# 05_LEDs.net
KiCad netlist of a schematic drawn in Altium Designer
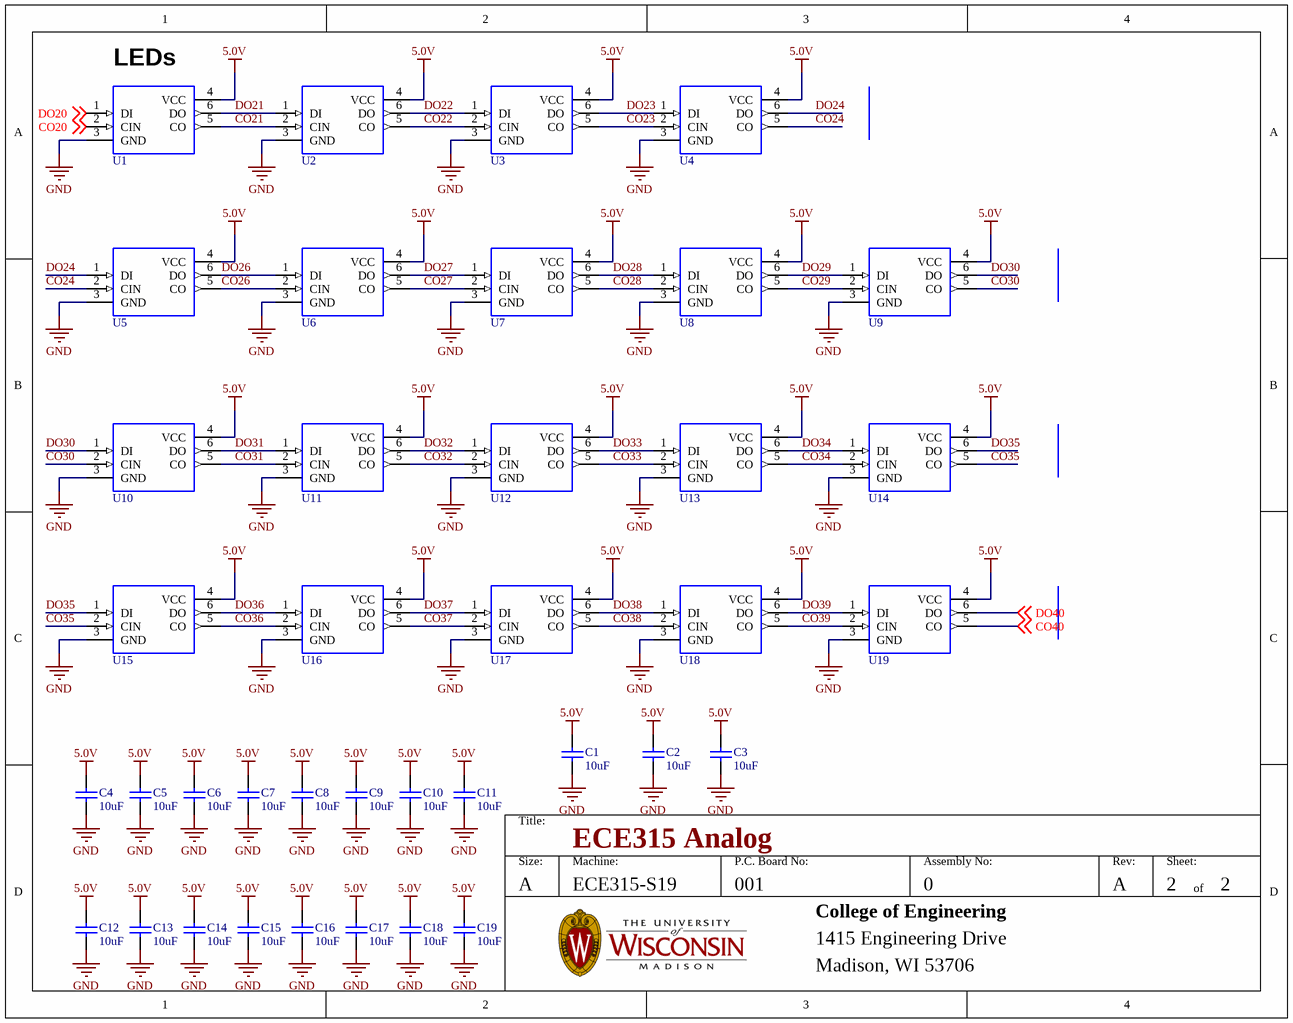
[diagram p0: 05_LEDs.SchDoc]

(export (version "E")
  (design (tool "Eeschema 10.0.6"))
  (components
    (comp (ref "C1")
      (value "10uF")
      (footprint "CAP_0805")
      (description "CAP CER 10UF 16V X7R 0805")
      (fields
        (field (name "MANUFACTURER") "Samsung")
        (field (name "MANUFACTURER PART NUMBER") "CL21A106KPCLQNC")
        (field (name "CAPACITANCE") "10uF")
      )
      (libsource (lib "ece315-2018-fall") (part "CAP_0805_U_010.00"))
    )
    (comp (ref "C2")
      (value "10uF")
      (footprint "CAP_0805")
      (description "CAP CER 10UF 16V X7R 0805")
      (fields
        (field (name "MANUFACTURER") "Samsung")
        (field (name "MANUFACTURER PART NUMBER") "CL21A106KPCLQNC")
        (field (name "CAPACITANCE") "10uF")
      )
      (libsource (lib "ece315-2018-fall") (part "CAP_0805_U_010.00"))
    )
    (comp (ref "C3")
      (value "10uF")
      (footprint "CAP_0805")
      (description "CAP CER 10UF 16V X7R 0805")
      (fields
        (field (name "MANUFACTURER") "Samsung")
        (field (name "MANUFACTURER PART NUMBER") "CL21A106KPCLQNC")
        (field (name "CAPACITANCE") "10uF")
      )
      (libsource (lib "ece315-2018-fall") (part "CAP_0805_U_010.00"))
    )
    (comp (ref "C4")
      (value "10uF")
      (footprint "CAP_0805")
      (description "CAP CER 10UF 16V X7R 0805")
      (fields
        (field (name "MANUFACTURER") "Samsung")
        (field (name "MANUFACTURER PART NUMBER") "CL21A106KPCLQNC")
        (field (name "CAPACITANCE") "10uF")
      )
      (libsource (lib "ece315-2018-fall") (part "CAP_0805_U_010.00"))
    )
    (comp (ref "C5")
      (value "10uF")
      (footprint "CAP_0805")
      (description "CAP CER 10UF 16V X7R 0805")
      (fields
        (field (name "MANUFACTURER") "Samsung")
        (field (name "MANUFACTURER PART NUMBER") "CL21A106KPCLQNC")
        (field (name "CAPACITANCE") "10uF")
      )
      (libsource (lib "ece315-2018-fall") (part "CAP_0805_U_010.00"))
    )
    (comp (ref "C6")
      (value "10uF")
      (footprint "CAP_0805")
      (description "CAP CER 10UF 16V X7R 0805")
      (fields
        (field (name "MANUFACTURER") "Samsung")
        (field (name "MANUFACTURER PART NUMBER") "CL21A106KPCLQNC")
        (field (name "CAPACITANCE") "10uF")
      )
      (libsource (lib "ece315-2018-fall") (part "CAP_0805_U_010.00"))
    )
    (comp (ref "C7")
      (value "10uF")
      (footprint "CAP_0805")
      (description "CAP CER 10UF 16V X7R 0805")
      (fields
        (field (name "MANUFACTURER") "Samsung")
        (field (name "MANUFACTURER PART NUMBER") "CL21A106KPCLQNC")
        (field (name "CAPACITANCE") "10uF")
      )
      (libsource (lib "ece315-2018-fall") (part "CAP_0805_U_010.00"))
    )
    (comp (ref "C8")
      (value "10uF")
      (footprint "CAP_0805")
      (description "CAP CER 10UF 16V X7R 0805")
      (fields
        (field (name "MANUFACTURER") "Samsung")
        (field (name "MANUFACTURER PART NUMBER") "CL21A106KPCLQNC")
        (field (name "CAPACITANCE") "10uF")
      )
      (libsource (lib "ece315-2018-fall") (part "CAP_0805_U_010.00"))
    )
    (comp (ref "C9")
      (value "10uF")
      (footprint "CAP_0805")
      (description "CAP CER 10UF 16V X7R 0805")
      (fields
        (field (name "MANUFACTURER") "Samsung")
        (field (name "MANUFACTURER PART NUMBER") "CL21A106KPCLQNC")
        (field (name "CAPACITANCE") "10uF")
      )
      (libsource (lib "ece315-2018-fall") (part "CAP_0805_U_010.00"))
    )
    (comp (ref "C10")
      (value "10uF")
      (footprint "CAP_0805")
      (description "CAP CER 10UF 16V X7R 0805")
      (fields
        (field (name "MANUFACTURER") "Samsung")
        (field (name "MANUFACTURER PART NUMBER") "CL21A106KPCLQNC")
        (field (name "CAPACITANCE") "10uF")
      )
      (libsource (lib "ece315-2018-fall") (part "CAP_0805_U_010.00"))
    )
    (comp (ref "C11")
      (value "10uF")
      (footprint "CAP_0805")
      (description "CAP CER 10UF 16V X7R 0805")
      (fields
        (field (name "MANUFACTURER") "Samsung")
        (field (name "MANUFACTURER PART NUMBER") "CL21A106KPCLQNC")
        (field (name "CAPACITANCE") "10uF")
      )
      (libsource (lib "ece315-2018-fall") (part "CAP_0805_U_010.00"))
    )
    (comp (ref "C12")
      (value "10uF")
      (footprint "CAP_0805")
      (description "CAP CER 10UF 16V X7R 0805")
      (fields
        (field (name "MANUFACTURER") "Samsung")
        (field (name "MANUFACTURER PART NUMBER") "CL21A106KPCLQNC")
        (field (name "CAPACITANCE") "10uF")
      )
      (libsource (lib "ece315-2018-fall") (part "CAP_0805_U_010.00"))
    )
    (comp (ref "C13")
      (value "10uF")
      (footprint "CAP_0805")
      (description "CAP CER 10UF 16V X7R 0805")
      (fields
        (field (name "MANUFACTURER") "Samsung")
        (field (name "MANUFACTURER PART NUMBER") "CL21A106KPCLQNC")
        (field (name "CAPACITANCE") "10uF")
      )
      (libsource (lib "ece315-2018-fall") (part "CAP_0805_U_010.00"))
    )
    (comp (ref "C14")
      (value "10uF")
      (footprint "CAP_0805")
      (description "CAP CER 10UF 16V X7R 0805")
      (fields
        (field (name "MANUFACTURER") "Samsung")
        (field (name "MANUFACTURER PART NUMBER") "CL21A106KPCLQNC")
        (field (name "CAPACITANCE") "10uF")
      )
      (libsource (lib "ece315-2018-fall") (part "CAP_0805_U_010.00"))
    )
    (comp (ref "C15")
      (value "10uF")
      (footprint "CAP_0805")
      (description "CAP CER 10UF 16V X7R 0805")
      (fields
        (field (name "MANUFACTURER") "Samsung")
        (field (name "MANUFACTURER PART NUMBER") "CL21A106KPCLQNC")
        (field (name "CAPACITANCE") "10uF")
      )
      (libsource (lib "ece315-2018-fall") (part "CAP_0805_U_010.00"))
    )
    (comp (ref "C16")
      (value "10uF")
      (footprint "CAP_0805")
      (description "CAP CER 10UF 16V X7R 0805")
      (fields
        (field (name "MANUFACTURER") "Samsung")
        (field (name "MANUFACTURER PART NUMBER") "CL21A106KPCLQNC")
        (field (name "CAPACITANCE") "10uF")
      )
      (libsource (lib "ece315-2018-fall") (part "CAP_0805_U_010.00"))
    )
    (comp (ref "C17")
      (value "10uF")
      (footprint "CAP_0805")
      (description "CAP CER 10UF 16V X7R 0805")
      (fields
        (field (name "MANUFACTURER") "Samsung")
        (field (name "MANUFACTURER PART NUMBER") "CL21A106KPCLQNC")
        (field (name "CAPACITANCE") "10uF")
      )
      (libsource (lib "ece315-2018-fall") (part "CAP_0805_U_010.00"))
    )
    (comp (ref "C18")
      (value "10uF")
      (footprint "CAP_0805")
      (description "CAP CER 10UF 16V X7R 0805")
      (fields
        (field (name "MANUFACTURER") "Samsung")
        (field (name "MANUFACTURER PART NUMBER") "CL21A106KPCLQNC")
        (field (name "CAPACITANCE") "10uF")
      )
      (libsource (lib "ece315-2018-fall") (part "CAP_0805_U_010.00"))
    )
    (comp (ref "C19")
      (value "10uF")
      (footprint "CAP_0805")
      (description "CAP CER 10UF 16V X7R 0805")
      (fields
        (field (name "MANUFACTURER") "Samsung")
        (field (name "MANUFACTURER PART NUMBER") "CL21A106KPCLQNC")
        (field (name "CAPACITANCE") "10uF")
      )
      (libsource (lib "ece315-2018-fall") (part "CAP_0805_U_010.00"))
    )
    (comp (ref "U1")
      (value "IC_APA102C")
      (footprint "APA102C")
      (description "APA102C LED")
      (libsource (lib "ece315-2018-fall") (part "IC_APA102C"))
    )
    (comp (ref "U2")
      (value "IC_APA102C")
      (footprint "APA102C")
      (description "APA102C LED")
      (libsource (lib "ece315-2018-fall") (part "IC_APA102C"))
    )
    (comp (ref "U3")
      (value "IC_APA102C")
      (footprint "APA102C")
      (description "APA102C LED")
      (libsource (lib "ece315-2018-fall") (part "IC_APA102C"))
    )
    (comp (ref "U4")
      (value "IC_APA102C")
      (footprint "APA102C")
      (description "APA102C LED")
      (libsource (lib "ece315-2018-fall") (part "IC_APA102C"))
    )
    (comp (ref "U5")
      (value "IC_APA102C")
      (footprint "APA102C")
      (description "APA102C LED")
      (libsource (lib "ece315-2018-fall") (part "IC_APA102C"))
    )
    (comp (ref "U6")
      (value "IC_APA102C")
      (footprint "APA102C")
      (description "APA102C LED")
      (libsource (lib "ece315-2018-fall") (part "IC_APA102C"))
    )
    (comp (ref "U7")
      (value "IC_APA102C")
      (footprint "APA102C")
      (description "APA102C LED")
      (libsource (lib "ece315-2018-fall") (part "IC_APA102C"))
    )
    (comp (ref "U8")
      (value "IC_APA102C")
      (footprint "APA102C")
      (description "APA102C LED")
      (libsource (lib "ece315-2018-fall") (part "IC_APA102C"))
    )
    (comp (ref "U9")
      (value "IC_APA102C")
      (footprint "APA102C")
      (description "APA102C LED")
      (libsource (lib "ece315-2018-fall") (part "IC_APA102C"))
    )
    (comp (ref "U10")
      (value "IC_APA102C")
      (footprint "APA102C")
      (description "APA102C LED")
      (libsource (lib "ece315-2018-fall") (part "IC_APA102C"))
    )
    (comp (ref "U11")
      (value "IC_APA102C")
      (footprint "APA102C")
      (description "APA102C LED")
      (libsource (lib "ece315-2018-fall") (part "IC_APA102C"))
    )
    (comp (ref "U12")
      (value "IC_APA102C")
      (footprint "APA102C")
      (description "APA102C LED")
      (libsource (lib "ece315-2018-fall") (part "IC_APA102C"))
    )
    (comp (ref "U13")
      (value "IC_APA102C")
      (footprint "APA102C")
      (description "APA102C LED")
      (libsource (lib "ece315-2018-fall") (part "IC_APA102C"))
    )
    (comp (ref "U14")
      (value "IC_APA102C")
      (footprint "APA102C")
      (description "APA102C LED")
      (libsource (lib "ece315-2018-fall") (part "IC_APA102C"))
    )
    (comp (ref "U15")
      (value "IC_APA102C")
      (footprint "APA102C")
      (description "APA102C LED")
      (libsource (lib "ece315-2018-fall") (part "IC_APA102C"))
    )
    (comp (ref "U16")
      (value "IC_APA102C")
      (footprint "APA102C")
      (description "APA102C LED")
      (libsource (lib "ece315-2018-fall") (part "IC_APA102C"))
    )
    (comp (ref "U17")
      (value "IC_APA102C")
      (footprint "APA102C")
      (description "APA102C LED")
      (libsource (lib "ece315-2018-fall") (part "IC_APA102C"))
    )
    (comp (ref "U18")
      (value "IC_APA102C")
      (footprint "APA102C")
      (description "APA102C LED")
      (libsource (lib "ece315-2018-fall") (part "IC_APA102C"))
    )
    (comp (ref "U19")
      (value "IC_APA102C")
      (footprint "APA102C")
      (description "APA102C LED")
      (libsource (lib "ece315-2018-fall") (part "IC_APA102C"))
    )
  )
  (nets
    (net (code "1") (name "/CO21") (class "Default")
      (node (ref "U1") (pin "5") (pinfunction "CO_5") (pintype "output"))
      (node (ref "U2") (pin "2") (pinfunction "CIN_2") (pintype "input"))
    )
    (net (code "2") (name "/CO22") (class "Default")
      (node (ref "U2") (pin "5") (pinfunction "CO_5") (pintype "output"))
      (node (ref "U3") (pin "2") (pinfunction "CIN_2") (pintype "input"))
    )
    (net (code "3") (name "/CO23") (class "Default")
      (node (ref "U3") (pin "5") (pinfunction "CO_5") (pintype "output"))
      (node (ref "U4") (pin "2") (pinfunction "CIN_2") (pintype "input"))
    )
    (net (code "4") (name "/CO24") (class "Default")
      (node (ref "U4") (pin "5") (pinfunction "CO_5") (pintype "output"))
      (node (ref "U5") (pin "2") (pinfunction "CIN_2") (pintype "input"))
    )
    (net (code "5") (name "/CO26") (class "Default")
      (node (ref "U5") (pin "5") (pinfunction "CO_5") (pintype "output"))
      (node (ref "U6") (pin "2") (pinfunction "CIN_2") (pintype "input"))
    )
    (net (code "6") (name "/CO27") (class "Default")
      (node (ref "U6") (pin "5") (pinfunction "CO_5") (pintype "output"))
      (node (ref "U7") (pin "2") (pinfunction "CIN_2") (pintype "input"))
    )
    (net (code "7") (name "/CO28") (class "Default")
      (node (ref "U7") (pin "5") (pinfunction "CO_5") (pintype "output"))
      (node (ref "U8") (pin "2") (pinfunction "CIN_2") (pintype "input"))
    )
    (net (code "8") (name "/CO29") (class "Default")
      (node (ref "U8") (pin "5") (pinfunction "CO_5") (pintype "output"))
      (node (ref "U9") (pin "2") (pinfunction "CIN_2") (pintype "input"))
    )
    (net (code "9") (name "/CO30") (class "Default")
      (node (ref "U10") (pin "2") (pinfunction "CIN_2") (pintype "input"))
      (node (ref "U9") (pin "5") (pinfunction "CO_5") (pintype "output"))
    )
    (net (code "10") (name "/CO31") (class "Default")
      (node (ref "U10") (pin "5") (pinfunction "CO_5") (pintype "output"))
      (node (ref "U11") (pin "2") (pinfunction "CIN_2") (pintype "input"))
    )
    (net (code "11") (name "/CO32") (class "Default")
      (node (ref "U11") (pin "5") (pinfunction "CO_5") (pintype "output"))
      (node (ref "U12") (pin "2") (pinfunction "CIN_2") (pintype "input"))
    )
    (net (code "12") (name "/CO33") (class "Default")
      (node (ref "U12") (pin "5") (pinfunction "CO_5") (pintype "output"))
      (node (ref "U13") (pin "2") (pinfunction "CIN_2") (pintype "input"))
    )
    (net (code "13") (name "/CO34") (class "Default")
      (node (ref "U13") (pin "5") (pinfunction "CO_5") (pintype "output"))
      (node (ref "U14") (pin "2") (pinfunction "CIN_2") (pintype "input"))
    )
    (net (code "14") (name "/CO35") (class "Default")
      (node (ref "U14") (pin "5") (pinfunction "CO_5") (pintype "output"))
      (node (ref "U15") (pin "2") (pinfunction "CIN_2") (pintype "input"))
    )
    (net (code "15") (name "/CO36") (class "Default")
      (node (ref "U15") (pin "5") (pinfunction "CO_5") (pintype "output"))
      (node (ref "U16") (pin "2") (pinfunction "CIN_2") (pintype "input"))
    )
    (net (code "16") (name "/CO37") (class "Default")
      (node (ref "U16") (pin "5") (pinfunction "CO_5") (pintype "output"))
      (node (ref "U17") (pin "2") (pinfunction "CIN_2") (pintype "input"))
    )
    (net (code "17") (name "/CO38") (class "Default")
      (node (ref "U17") (pin "5") (pinfunction "CO_5") (pintype "output"))
      (node (ref "U18") (pin "2") (pinfunction "CIN_2") (pintype "input"))
    )
    (net (code "18") (name "/CO39") (class "Default")
      (node (ref "U18") (pin "5") (pinfunction "CO_5") (pintype "output"))
      (node (ref "U19") (pin "2") (pinfunction "CIN_2") (pintype "input"))
    )
    (net (code "19") (name "/DO21") (class "Default")
      (node (ref "U1") (pin "6") (pinfunction "DO_6") (pintype "output"))
      (node (ref "U2") (pin "1") (pinfunction "DI_1") (pintype "input"))
    )
    (net (code "20") (name "/DO22") (class "Default")
      (node (ref "U2") (pin "6") (pinfunction "DO_6") (pintype "output"))
      (node (ref "U3") (pin "1") (pinfunction "DI_1") (pintype "input"))
    )
    (net (code "21") (name "/DO23") (class "Default")
      (node (ref "U3") (pin "6") (pinfunction "DO_6") (pintype "output"))
      (node (ref "U4") (pin "1") (pinfunction "DI_1") (pintype "input"))
    )
    (net (code "22") (name "/DO24") (class "Default")
      (node (ref "U4") (pin "6") (pinfunction "DO_6") (pintype "output"))
      (node (ref "U5") (pin "1") (pinfunction "DI_1") (pintype "input"))
    )
    (net (code "23") (name "/DO26") (class "Default")
      (node (ref "U5") (pin "6") (pinfunction "DO_6") (pintype "output"))
      (node (ref "U6") (pin "1") (pinfunction "DI_1") (pintype "input"))
    )
    (net (code "24") (name "/DO27") (class "Default")
      (node (ref "U6") (pin "6") (pinfunction "DO_6") (pintype "output"))
      (node (ref "U7") (pin "1") (pinfunction "DI_1") (pintype "input"))
    )
    (net (code "25") (name "/DO28") (class "Default")
      (node (ref "U7") (pin "6") (pinfunction "DO_6") (pintype "output"))
      (node (ref "U8") (pin "1") (pinfunction "DI_1") (pintype "input"))
    )
    (net (code "26") (name "/DO29") (class "Default")
      (node (ref "U8") (pin "6") (pinfunction "DO_6") (pintype "output"))
      (node (ref "U9") (pin "1") (pinfunction "DI_1") (pintype "input"))
    )
    (net (code "27") (name "/DO30") (class "Default")
      (node (ref "U10") (pin "1") (pinfunction "DI_1") (pintype "input"))
      (node (ref "U9") (pin "6") (pinfunction "DO_6") (pintype "output"))
    )
    (net (code "28") (name "/DO31") (class "Default")
      (node (ref "U10") (pin "6") (pinfunction "DO_6") (pintype "output"))
      (node (ref "U11") (pin "1") (pinfunction "DI_1") (pintype "input"))
    )
    (net (code "29") (name "/DO32") (class "Default")
      (node (ref "U11") (pin "6") (pinfunction "DO_6") (pintype "output"))
      (node (ref "U12") (pin "1") (pinfunction "DI_1") (pintype "input"))
    )
    (net (code "30") (name "/DO33") (class "Default")
      (node (ref "U12") (pin "6") (pinfunction "DO_6") (pintype "output"))
      (node (ref "U13") (pin "1") (pinfunction "DI_1") (pintype "input"))
    )
    (net (code "31") (name "/DO34") (class "Default")
      (node (ref "U13") (pin "6") (pinfunction "DO_6") (pintype "output"))
      (node (ref "U14") (pin "1") (pinfunction "DI_1") (pintype "input"))
    )
    (net (code "32") (name "/DO35") (class "Default")
      (node (ref "U14") (pin "6") (pinfunction "DO_6") (pintype "output"))
      (node (ref "U15") (pin "1") (pinfunction "DI_1") (pintype "input"))
    )
    (net (code "33") (name "/DO36") (class "Default")
      (node (ref "U15") (pin "6") (pinfunction "DO_6") (pintype "output"))
      (node (ref "U16") (pin "1") (pinfunction "DI_1") (pintype "input"))
    )
    (net (code "34") (name "/DO37") (class "Default")
      (node (ref "U16") (pin "6") (pinfunction "DO_6") (pintype "output"))
      (node (ref "U17") (pin "1") (pinfunction "DI_1") (pintype "input"))
    )
    (net (code "35") (name "/DO38") (class "Default")
      (node (ref "U17") (pin "6") (pinfunction "DO_6") (pintype "output"))
      (node (ref "U18") (pin "1") (pinfunction "DI_1") (pintype "input"))
    )
    (net (code "36") (name "/DO39") (class "Default")
      (node (ref "U18") (pin "6") (pinfunction "DO_6") (pintype "output"))
      (node (ref "U19") (pin "1") (pinfunction "DI_1") (pintype "input"))
    )
    (net (code "37") (name "5.0V") (class "Default")
      (node (ref "C1") (pin "2") (pinfunction "2_2") (pintype "passive"))
      (node (ref "C10") (pin "2") (pinfunction "2_2") (pintype "passive"))
      (node (ref "C11") (pin "2") (pinfunction "2_2") (pintype "passive"))
      (node (ref "C12") (pin "2") (pinfunction "2_2") (pintype "passive"))
      (node (ref "C13") (pin "2") (pinfunction "2_2") (pintype "passive"))
      (node (ref "C14") (pin "2") (pinfunction "2_2") (pintype "passive"))
      (node (ref "C15") (pin "2") (pinfunction "2_2") (pintype "passive"))
      (node (ref "C16") (pin "2") (pinfunction "2_2") (pintype "passive"))
      (node (ref "C17") (pin "2") (pinfunction "2_2") (pintype "passive"))
      (node (ref "C18") (pin "2") (pinfunction "2_2") (pintype "passive"))
      (node (ref "C19") (pin "2") (pinfunction "2_2") (pintype "passive"))
      (node (ref "C2") (pin "2") (pinfunction "2_2") (pintype "passive"))
      (node (ref "C3") (pin "2") (pinfunction "2_2") (pintype "passive"))
      (node (ref "C4") (pin "2") (pinfunction "2_2") (pintype "passive"))
      (node (ref "C5") (pin "2") (pinfunction "2_2") (pintype "passive"))
      (node (ref "C6") (pin "2") (pinfunction "2_2") (pintype "passive"))
      (node (ref "C7") (pin "2") (pinfunction "2_2") (pintype "passive"))
      (node (ref "C8") (pin "2") (pinfunction "2_2") (pintype "passive"))
      (node (ref "C9") (pin "2") (pinfunction "2_2") (pintype "passive"))
      (node (ref "U1") (pin "4") (pinfunction "VCC_4") (pintype "power_in"))
      (node (ref "U10") (pin "4") (pinfunction "VCC_4") (pintype "power_in"))
      (node (ref "U11") (pin "4") (pinfunction "VCC_4") (pintype "power_in"))
      (node (ref "U12") (pin "4") (pinfunction "VCC_4") (pintype "power_in"))
      (node (ref "U13") (pin "4") (pinfunction "VCC_4") (pintype "power_in"))
      (node (ref "U14") (pin "4") (pinfunction "VCC_4") (pintype "power_in"))
      (node (ref "U15") (pin "4") (pinfunction "VCC_4") (pintype "power_in"))
      (node (ref "U16") (pin "4") (pinfunction "VCC_4") (pintype "power_in"))
      (node (ref "U17") (pin "4") (pinfunction "VCC_4") (pintype "power_in"))
      (node (ref "U18") (pin "4") (pinfunction "VCC_4") (pintype "power_in"))
      (node (ref "U19") (pin "4") (pinfunction "VCC_4") (pintype "power_in"))
      (node (ref "U2") (pin "4") (pinfunction "VCC_4") (pintype "power_in"))
      (node (ref "U3") (pin "4") (pinfunction "VCC_4") (pintype "power_in"))
      (node (ref "U4") (pin "4") (pinfunction "VCC_4") (pintype "power_in"))
      (node (ref "U5") (pin "4") (pinfunction "VCC_4") (pintype "power_in"))
      (node (ref "U6") (pin "4") (pinfunction "VCC_4") (pintype "power_in"))
      (node (ref "U7") (pin "4") (pinfunction "VCC_4") (pintype "power_in"))
      (node (ref "U8") (pin "4") (pinfunction "VCC_4") (pintype "power_in"))
      (node (ref "U9") (pin "4") (pinfunction "VCC_4") (pintype "power_in"))
    )
    (net (code "38") (name "CO20") (class "Default")
      (node (ref "U1") (pin "2") (pinfunction "CIN_2") (pintype "input"))
    )
    (net (code "39") (name "CO40") (class "Default")
      (node (ref "U19") (pin "5") (pinfunction "CO_5") (pintype "output"))
    )
    (net (code "40") (name "DO20") (class "Default")
      (node (ref "U1") (pin "1") (pinfunction "DI_1") (pintype "input"))
    )
    (net (code "41") (name "DO40") (class "Default")
      (node (ref "U19") (pin "6") (pinfunction "DO_6") (pintype "output"))
    )
    (net (code "42") (name "GND") (class "Default")
      (node (ref "C1") (pin "1") (pinfunction "1_1") (pintype "passive"))
      (node (ref "C10") (pin "1") (pinfunction "1_1") (pintype "passive"))
      (node (ref "C11") (pin "1") (pinfunction "1_1") (pintype "passive"))
      (node (ref "C12") (pin "1") (pinfunction "1_1") (pintype "passive"))
      (node (ref "C13") (pin "1") (pinfunction "1_1") (pintype "passive"))
      (node (ref "C14") (pin "1") (pinfunction "1_1") (pintype "passive"))
      (node (ref "C15") (pin "1") (pinfunction "1_1") (pintype "passive"))
      (node (ref "C16") (pin "1") (pinfunction "1_1") (pintype "passive"))
      (node (ref "C17") (pin "1") (pinfunction "1_1") (pintype "passive"))
      (node (ref "C18") (pin "1") (pinfunction "1_1") (pintype "passive"))
      (node (ref "C19") (pin "1") (pinfunction "1_1") (pintype "passive"))
      (node (ref "C2") (pin "1") (pinfunction "1_1") (pintype "passive"))
      (node (ref "C3") (pin "1") (pinfunction "1_1") (pintype "passive"))
      (node (ref "C4") (pin "1") (pinfunction "1_1") (pintype "passive"))
      (node (ref "C5") (pin "1") (pinfunction "1_1") (pintype "passive"))
      (node (ref "C6") (pin "1") (pinfunction "1_1") (pintype "passive"))
      (node (ref "C7") (pin "1") (pinfunction "1_1") (pintype "passive"))
      (node (ref "C8") (pin "1") (pinfunction "1_1") (pintype "passive"))
      (node (ref "C9") (pin "1") (pinfunction "1_1") (pintype "passive"))
      (node (ref "U1") (pin "3") (pinfunction "GND_3") (pintype "power_in"))
      (node (ref "U10") (pin "3") (pinfunction "GND_3") (pintype "power_in"))
      (node (ref "U11") (pin "3") (pinfunction "GND_3") (pintype "power_in"))
      (node (ref "U12") (pin "3") (pinfunction "GND_3") (pintype "power_in"))
      (node (ref "U13") (pin "3") (pinfunction "GND_3") (pintype "power_in"))
      (node (ref "U14") (pin "3") (pinfunction "GND_3") (pintype "power_in"))
      (node (ref "U15") (pin "3") (pinfunction "GND_3") (pintype "power_in"))
      (node (ref "U16") (pin "3") (pinfunction "GND_3") (pintype "power_in"))
      (node (ref "U17") (pin "3") (pinfunction "GND_3") (pintype "power_in"))
      (node (ref "U18") (pin "3") (pinfunction "GND_3") (pintype "power_in"))
      (node (ref "U19") (pin "3") (pinfunction "GND_3") (pintype "power_in"))
      (node (ref "U2") (pin "3") (pinfunction "GND_3") (pintype "power_in"))
      (node (ref "U3") (pin "3") (pinfunction "GND_3") (pintype "power_in"))
      (node (ref "U4") (pin "3") (pinfunction "GND_3") (pintype "power_in"))
      (node (ref "U5") (pin "3") (pinfunction "GND_3") (pintype "power_in"))
      (node (ref "U6") (pin "3") (pinfunction "GND_3") (pintype "power_in"))
      (node (ref "U7") (pin "3") (pinfunction "GND_3") (pintype "power_in"))
      (node (ref "U8") (pin "3") (pinfunction "GND_3") (pintype "power_in"))
      (node (ref "U9") (pin "3") (pinfunction "GND_3") (pintype "power_in"))
    )
  )
)
